# tester_adapter_board.net
KiCad netlist of a schematic drawn in EAGLE
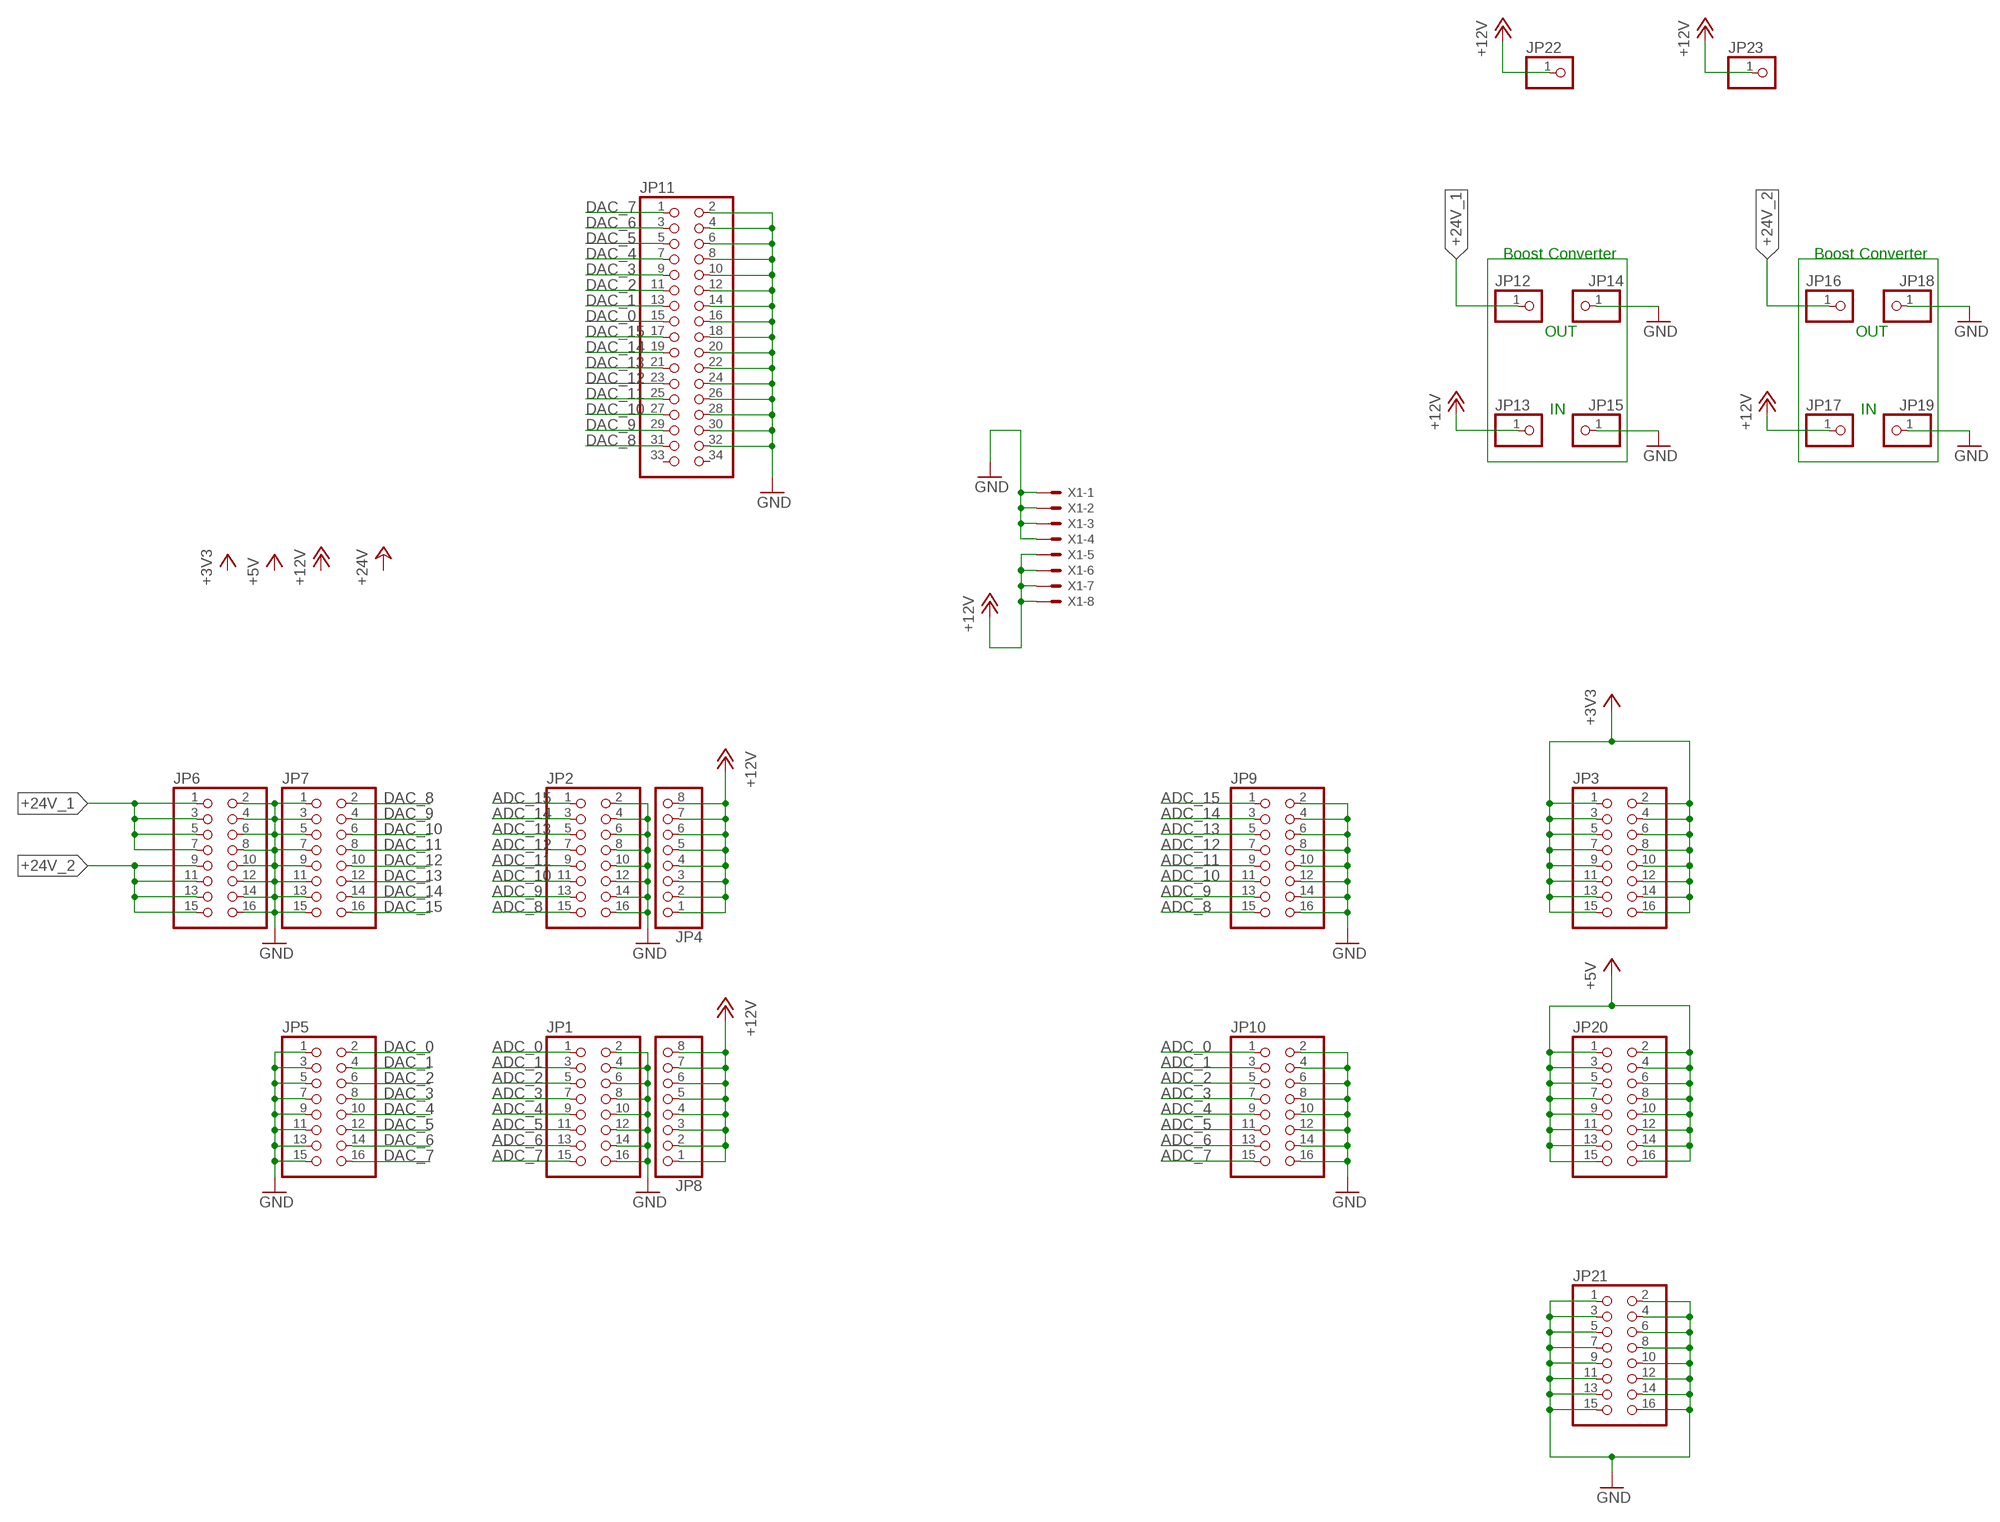
[diagram p0: schematic, sheet 1]

(export (version "E")
  (design (tool "Eeschema 10.0.6"))
  (components
    (comp (ref "JP1")
      (value "PINHD-2X8")
      (footprint "eagle-import:2X08")
      (libsource (lib "eagle-import") (part "PINHD-2X8"))
    )
    (comp (ref "JP2")
      (value "PINHD-2X8")
      (footprint "eagle-import:2X08")
      (libsource (lib "eagle-import") (part "PINHD-2X8"))
    )
    (comp (ref "JP3")
      (value "PINHD-2X8")
      (footprint "eagle-import:2X08")
      (libsource (lib "eagle-import") (part "PINHD-2X8"))
    )
    (comp (ref "JP4")
      (value "PINHD-1X08_2.54-S")
      (footprint "eagle-import:1X08-S")
      (libsource (lib "eagle-import") (part "PINHD-1X08_2.54-S"))
    )
    (comp (ref "JP5")
      (value "PINHD-2X8")
      (footprint "eagle-import:2X08")
      (libsource (lib "eagle-import") (part "PINHD-2X8"))
    )
    (comp (ref "JP6")
      (value "PINHD-2X8")
      (footprint "eagle-import:2X08")
      (libsource (lib "eagle-import") (part "PINHD-2X8"))
    )
    (comp (ref "JP7")
      (value "PINHD-2X8")
      (footprint "eagle-import:2X08")
      (libsource (lib "eagle-import") (part "PINHD-2X8"))
    )
    (comp (ref "JP8")
      (value "PINHD-1X08_2.54-S")
      (footprint "eagle-import:1X08-S")
      (libsource (lib "eagle-import") (part "PINHD-1X08_2.54-S"))
    )
    (comp (ref "JP9")
      (value "PINHD-2X8")
      (footprint "eagle-import:2X08")
      (libsource (lib "eagle-import") (part "PINHD-2X8"))
    )
    (comp (ref "JP10")
      (value "PINHD-2X8")
      (footprint "eagle-import:2X08")
      (libsource (lib "eagle-import") (part "PINHD-2X8"))
    )
    (comp (ref "JP11")
      (value "PINHD-2X17")
      (footprint "eagle-import:2X17")
      (libsource (lib "eagle-import") (part "PINHD-2X17"))
    )
    (comp (ref "JP12")
      (value "PINHD-1X01_2.54")
      (footprint "eagle-import:1X01")
      (libsource (lib "eagle-import") (part "PINHD-1X01_2.54"))
    )
    (comp (ref "JP13")
      (value "PINHD-1X01_2.54")
      (footprint "eagle-import:1X01")
      (libsource (lib "eagle-import") (part "PINHD-1X01_2.54"))
    )
    (comp (ref "JP14")
      (value "PINHD-1X01_2.54-S")
      (footprint "eagle-import:1X01-S")
      (libsource (lib "eagle-import") (part "PINHD-1X01_2.54-S"))
    )
    (comp (ref "JP15")
      (value "PINHD-1X01_2.54-S")
      (footprint "eagle-import:1X01-S")
      (libsource (lib "eagle-import") (part "PINHD-1X01_2.54-S"))
    )
    (comp (ref "JP16")
      (value "PINHD-1X01_2.54")
      (footprint "eagle-import:1X01")
      (libsource (lib "eagle-import") (part "PINHD-1X01_2.54"))
    )
    (comp (ref "JP17")
      (value "PINHD-1X01_2.54")
      (footprint "eagle-import:1X01")
      (libsource (lib "eagle-import") (part "PINHD-1X01_2.54"))
    )
    (comp (ref "JP18")
      (value "PINHD-1X01_2.54-S")
      (footprint "eagle-import:1X01-S")
      (libsource (lib "eagle-import") (part "PINHD-1X01_2.54-S"))
    )
    (comp (ref "JP19")
      (value "PINHD-1X01_2.54-S")
      (footprint "eagle-import:1X01-S")
      (libsource (lib "eagle-import") (part "PINHD-1X01_2.54-S"))
    )
    (comp (ref "JP20")
      (value "PINHD-2X8")
      (footprint "eagle-import:2X08")
      (libsource (lib "eagle-import") (part "PINHD-2X8"))
    )
    (comp (ref "JP21")
      (value "PINHD-2X8")
      (footprint "eagle-import:2X08")
      (libsource (lib "eagle-import") (part "PINHD-2X8"))
    )
    (comp (ref "JP22")
      (value "PINHD-1X01_2.54-SMD")
      (footprint "eagle-import:1X01SMD")
      (libsource (lib "eagle-import") (part "PINHD-1X01_2.54-SMD"))
    )
    (comp (ref "JP23")
      (value "PINHD-1X01_2.54-SMD")
      (footprint "eagle-import:1X01SMD")
      (libsource (lib "eagle-import") (part "PINHD-1X01_2.54-SMD"))
    )
    (comp (ref "X1")
      (value "5566-8")
      (footprint "eagle-import:5566-8")
      (fields (field (name "MF") "MOLEX"))
      (libsource (lib "eagle-import") (part "5566-8"))
    )
  )
  (nets
    (net (code "1") (name "+3V3") (class "Default")
      (node (ref "JP3") (pin "1") (pinfunction "1_1") (pintype "passive"))
      (node (ref "JP3") (pin "10") (pinfunction "10_10") (pintype "passive"))
      (node (ref "JP3") (pin "11") (pinfunction "11_11") (pintype "passive"))
      (node (ref "JP3") (pin "12") (pinfunction "12_12") (pintype "passive"))
      (node (ref "JP3") (pin "13") (pinfunction "13_13") (pintype "passive"))
      (node (ref "JP3") (pin "14") (pinfunction "14_14") (pintype "passive"))
      (node (ref "JP3") (pin "15") (pinfunction "15_15") (pintype "passive"))
      (node (ref "JP3") (pin "16") (pinfunction "16_16") (pintype "passive"))
      (node (ref "JP3") (pin "2") (pinfunction "2_2") (pintype "passive"))
      (node (ref "JP3") (pin "3") (pinfunction "3_3") (pintype "passive"))
      (node (ref "JP3") (pin "4") (pinfunction "4_4") (pintype "passive"))
      (node (ref "JP3") (pin "5") (pinfunction "5_5") (pintype "passive"))
      (node (ref "JP3") (pin "6") (pinfunction "6_6") (pintype "passive"))
      (node (ref "JP3") (pin "7") (pinfunction "7_7") (pintype "passive"))
      (node (ref "JP3") (pin "8") (pinfunction "8_8") (pintype "passive"))
      (node (ref "JP3") (pin "9") (pinfunction "9_9") (pintype "passive"))
    )
    (net (code "2") (name "+5V") (class "Default")
      (node (ref "JP20") (pin "1") (pinfunction "1_1") (pintype "passive"))
      (node (ref "JP20") (pin "10") (pinfunction "10_10") (pintype "passive"))
      (node (ref "JP20") (pin "11") (pinfunction "11_11") (pintype "passive"))
      (node (ref "JP20") (pin "12") (pinfunction "12_12") (pintype "passive"))
      (node (ref "JP20") (pin "13") (pinfunction "13_13") (pintype "passive"))
      (node (ref "JP20") (pin "14") (pinfunction "14_14") (pintype "passive"))
      (node (ref "JP20") (pin "15") (pinfunction "15_15") (pintype "passive"))
      (node (ref "JP20") (pin "16") (pinfunction "16_16") (pintype "passive"))
      (node (ref "JP20") (pin "2") (pinfunction "2_2") (pintype "passive"))
      (node (ref "JP20") (pin "3") (pinfunction "3_3") (pintype "passive"))
      (node (ref "JP20") (pin "4") (pinfunction "4_4") (pintype "passive"))
      (node (ref "JP20") (pin "5") (pinfunction "5_5") (pintype "passive"))
      (node (ref "JP20") (pin "6") (pinfunction "6_6") (pintype "passive"))
      (node (ref "JP20") (pin "7") (pinfunction "7_7") (pintype "passive"))
      (node (ref "JP20") (pin "8") (pinfunction "8_8") (pintype "passive"))
      (node (ref "JP20") (pin "9") (pinfunction "9_9") (pintype "passive"))
    )
    (net (code "3") (name "+12V") (class "Default")
      (node (ref "JP13") (pin "1") (pinfunction "1_1") (pintype "passive"))
      (node (ref "JP17") (pin "1") (pinfunction "1_1") (pintype "passive"))
      (node (ref "JP22") (pin "1") (pinfunction "1_1") (pintype "passive"))
      (node (ref "JP23") (pin "1") (pinfunction "1_1") (pintype "passive"))
      (node (ref "JP4") (pin "1") (pinfunction "1_1") (pintype "passive"))
      (node (ref "JP4") (pin "2") (pinfunction "2_2") (pintype "passive"))
      (node (ref "JP4") (pin "3") (pinfunction "3_3") (pintype "passive"))
      (node (ref "JP4") (pin "4") (pinfunction "4_4") (pintype "passive"))
      (node (ref "JP4") (pin "5") (pinfunction "5_5") (pintype "passive"))
      (node (ref "JP4") (pin "6") (pinfunction "6_6") (pintype "passive"))
      (node (ref "JP4") (pin "7") (pinfunction "7_7") (pintype "passive"))
      (node (ref "JP4") (pin "8") (pinfunction "8_8") (pintype "passive"))
      (node (ref "JP8") (pin "1") (pinfunction "1_1") (pintype "passive"))
      (node (ref "JP8") (pin "2") (pinfunction "2_2") (pintype "passive"))
      (node (ref "JP8") (pin "3") (pinfunction "3_3") (pintype "passive"))
      (node (ref "JP8") (pin "4") (pinfunction "4_4") (pintype "passive"))
      (node (ref "JP8") (pin "5") (pinfunction "5_5") (pintype "passive"))
      (node (ref "JP8") (pin "6") (pinfunction "6_6") (pintype "passive"))
      (node (ref "JP8") (pin "7") (pinfunction "7_7") (pintype "passive"))
      (node (ref "JP8") (pin "8") (pinfunction "8_8") (pintype "passive"))
      (node (ref "X1") (pin "5") (pinfunction "S_5") (pintype "passive"))
      (node (ref "X1") (pin "6") (pinfunction "S_6") (pintype "passive"))
      (node (ref "X1") (pin "7") (pinfunction "S_7") (pintype "passive"))
      (node (ref "X1") (pin "8") (pinfunction "S_8") (pintype "passive"))
    )
    (net (code "5") (name "+24V_1") (class "Default")
      (node (ref "JP12") (pin "1") (pinfunction "1_1") (pintype "passive"))
      (node (ref "JP6") (pin "1") (pinfunction "1_1") (pintype "passive"))
      (node (ref "JP6") (pin "3") (pinfunction "3_3") (pintype "passive"))
      (node (ref "JP6") (pin "5") (pinfunction "5_5") (pintype "passive"))
      (node (ref "JP6") (pin "7") (pinfunction "7_7") (pintype "passive"))
    )
    (net (code "6") (name "+24V_2") (class "Default")
      (node (ref "JP16") (pin "1") (pinfunction "1_1") (pintype "passive"))
      (node (ref "JP6") (pin "11") (pinfunction "11_11") (pintype "passive"))
      (node (ref "JP6") (pin "13") (pinfunction "13_13") (pintype "passive"))
      (node (ref "JP6") (pin "15") (pinfunction "15_15") (pintype "passive"))
      (node (ref "JP6") (pin "9") (pinfunction "9_9") (pintype "passive"))
    )
    (net (code "7") (name "/ADC_0") (class "Default")
      (node (ref "JP1") (pin "1") (pinfunction "1_1") (pintype "passive"))
      (node (ref "JP10") (pin "1") (pinfunction "1_1") (pintype "passive"))
    )
    (net (code "8") (name "/ADC_1") (class "Default")
      (node (ref "JP1") (pin "3") (pinfunction "3_3") (pintype "passive"))
      (node (ref "JP10") (pin "3") (pinfunction "3_3") (pintype "passive"))
    )
    (net (code "9") (name "/ADC_2") (class "Default")
      (node (ref "JP1") (pin "5") (pinfunction "5_5") (pintype "passive"))
      (node (ref "JP10") (pin "5") (pinfunction "5_5") (pintype "passive"))
    )
    (net (code "10") (name "/ADC_3") (class "Default")
      (node (ref "JP1") (pin "7") (pinfunction "7_7") (pintype "passive"))
      (node (ref "JP10") (pin "7") (pinfunction "7_7") (pintype "passive"))
    )
    (net (code "11") (name "/ADC_4") (class "Default")
      (node (ref "JP1") (pin "9") (pinfunction "9_9") (pintype "passive"))
      (node (ref "JP10") (pin "9") (pinfunction "9_9") (pintype "passive"))
    )
    (net (code "12") (name "/ADC_5") (class "Default")
      (node (ref "JP1") (pin "11") (pinfunction "11_11") (pintype "passive"))
      (node (ref "JP10") (pin "11") (pinfunction "11_11") (pintype "passive"))
    )
    (net (code "13") (name "/ADC_6") (class "Default")
      (node (ref "JP1") (pin "13") (pinfunction "13_13") (pintype "passive"))
      (node (ref "JP10") (pin "13") (pinfunction "13_13") (pintype "passive"))
    )
    (net (code "14") (name "/ADC_7") (class "Default")
      (node (ref "JP1") (pin "15") (pinfunction "15_15") (pintype "passive"))
      (node (ref "JP10") (pin "15") (pinfunction "15_15") (pintype "passive"))
    )
    (net (code "15") (name "/ADC_8") (class "Default")
      (node (ref "JP2") (pin "15") (pinfunction "15_15") (pintype "passive"))
      (node (ref "JP9") (pin "15") (pinfunction "15_15") (pintype "passive"))
    )
    (net (code "16") (name "/ADC_9") (class "Default")
      (node (ref "JP2") (pin "13") (pinfunction "13_13") (pintype "passive"))
      (node (ref "JP9") (pin "13") (pinfunction "13_13") (pintype "passive"))
    )
    (net (code "17") (name "/ADC_10") (class "Default")
      (node (ref "JP2") (pin "11") (pinfunction "11_11") (pintype "passive"))
      (node (ref "JP9") (pin "11") (pinfunction "11_11") (pintype "passive"))
    )
    (net (code "18") (name "/ADC_11") (class "Default")
      (node (ref "JP2") (pin "9") (pinfunction "9_9") (pintype "passive"))
      (node (ref "JP9") (pin "9") (pinfunction "9_9") (pintype "passive"))
    )
    (net (code "19") (name "/ADC_12") (class "Default")
      (node (ref "JP2") (pin "7") (pinfunction "7_7") (pintype "passive"))
      (node (ref "JP9") (pin "7") (pinfunction "7_7") (pintype "passive"))
    )
    (net (code "20") (name "/ADC_13") (class "Default")
      (node (ref "JP2") (pin "5") (pinfunction "5_5") (pintype "passive"))
      (node (ref "JP9") (pin "5") (pinfunction "5_5") (pintype "passive"))
    )
    (net (code "21") (name "/ADC_14") (class "Default")
      (node (ref "JP2") (pin "3") (pinfunction "3_3") (pintype "passive"))
      (node (ref "JP9") (pin "3") (pinfunction "3_3") (pintype "passive"))
    )
    (net (code "22") (name "/ADC_15") (class "Default")
      (node (ref "JP2") (pin "1") (pinfunction "1_1") (pintype "passive"))
      (node (ref "JP9") (pin "1") (pinfunction "1_1") (pintype "passive"))
    )
    (net (code "23") (name "/DAC_0") (class "Default")
      (node (ref "JP11") (pin "15") (pinfunction "15_15") (pintype "passive"))
      (node (ref "JP5") (pin "2") (pinfunction "2_2") (pintype "passive"))
    )
    (net (code "24") (name "/DAC_1") (class "Default")
      (node (ref "JP11") (pin "13") (pinfunction "13_13") (pintype "passive"))
      (node (ref "JP5") (pin "4") (pinfunction "4_4") (pintype "passive"))
    )
    (net (code "25") (name "/DAC_2") (class "Default")
      (node (ref "JP11") (pin "11") (pinfunction "11_11") (pintype "passive"))
      (node (ref "JP5") (pin "6") (pinfunction "6_6") (pintype "passive"))
    )
    (net (code "26") (name "/DAC_3") (class "Default")
      (node (ref "JP11") (pin "9") (pinfunction "9_9") (pintype "passive"))
      (node (ref "JP5") (pin "8") (pinfunction "8_8") (pintype "passive"))
    )
    (net (code "27") (name "/DAC_4") (class "Default")
      (node (ref "JP11") (pin "7") (pinfunction "7_7") (pintype "passive"))
      (node (ref "JP5") (pin "10") (pinfunction "10_10") (pintype "passive"))
    )
    (net (code "28") (name "/DAC_5") (class "Default")
      (node (ref "JP11") (pin "5") (pinfunction "5_5") (pintype "passive"))
      (node (ref "JP5") (pin "12") (pinfunction "12_12") (pintype "passive"))
    )
    (net (code "29") (name "/DAC_6") (class "Default")
      (node (ref "JP11") (pin "3") (pinfunction "3_3") (pintype "passive"))
      (node (ref "JP5") (pin "14") (pinfunction "14_14") (pintype "passive"))
    )
    (net (code "30") (name "/DAC_7") (class "Default")
      (node (ref "JP11") (pin "1") (pinfunction "1_1") (pintype "passive"))
      (node (ref "JP5") (pin "16") (pinfunction "16_16") (pintype "passive"))
    )
    (net (code "31") (name "/DAC_8") (class "Default")
      (node (ref "JP11") (pin "31") (pinfunction "31_31") (pintype "passive"))
      (node (ref "JP7") (pin "2") (pinfunction "2_2") (pintype "passive"))
    )
    (net (code "32") (name "/DAC_9") (class "Default")
      (node (ref "JP11") (pin "29") (pinfunction "29_29") (pintype "passive"))
      (node (ref "JP7") (pin "4") (pinfunction "4_4") (pintype "passive"))
    )
    (net (code "33") (name "/DAC_10") (class "Default")
      (node (ref "JP11") (pin "27") (pinfunction "27_27") (pintype "passive"))
      (node (ref "JP7") (pin "6") (pinfunction "6_6") (pintype "passive"))
    )
    (net (code "34") (name "/DAC_11") (class "Default")
      (node (ref "JP11") (pin "25") (pinfunction "25_25") (pintype "passive"))
      (node (ref "JP7") (pin "8") (pinfunction "8_8") (pintype "passive"))
    )
    (net (code "35") (name "/DAC_12") (class "Default")
      (node (ref "JP11") (pin "23") (pinfunction "23_23") (pintype "passive"))
      (node (ref "JP7") (pin "10") (pinfunction "10_10") (pintype "passive"))
    )
    (net (code "36") (name "/DAC_13") (class "Default")
      (node (ref "JP11") (pin "21") (pinfunction "21_21") (pintype "passive"))
      (node (ref "JP7") (pin "12") (pinfunction "12_12") (pintype "passive"))
    )
    (net (code "37") (name "/DAC_14") (class "Default")
      (node (ref "JP11") (pin "19") (pinfunction "19_19") (pintype "passive"))
      (node (ref "JP7") (pin "14") (pinfunction "14_14") (pintype "passive"))
    )
    (net (code "38") (name "/DAC_15") (class "Default")
      (node (ref "JP11") (pin "17") (pinfunction "17_17") (pintype "passive"))
      (node (ref "JP7") (pin "16") (pinfunction "16_16") (pintype "passive"))
    )
    (net (code "39") (name "GND") (class "Default")
      (node (ref "JP1") (pin "10") (pinfunction "10_10") (pintype "passive"))
      (node (ref "JP1") (pin "12") (pinfunction "12_12") (pintype "passive"))
      (node (ref "JP1") (pin "14") (pinfunction "14_14") (pintype "passive"))
      (node (ref "JP1") (pin "16") (pinfunction "16_16") (pintype "passive"))
      (node (ref "JP1") (pin "2") (pinfunction "2_2") (pintype "passive"))
      (node (ref "JP1") (pin "4") (pinfunction "4_4") (pintype "passive"))
      (node (ref "JP1") (pin "6") (pinfunction "6_6") (pintype "passive"))
      (node (ref "JP1") (pin "8") (pinfunction "8_8") (pintype "passive"))
      (node (ref "JP10") (pin "10") (pinfunction "10_10") (pintype "passive"))
      (node (ref "JP10") (pin "12") (pinfunction "12_12") (pintype "passive"))
      (node (ref "JP10") (pin "14") (pinfunction "14_14") (pintype "passive"))
      (node (ref "JP10") (pin "16") (pinfunction "16_16") (pintype "passive"))
      (node (ref "JP10") (pin "2") (pinfunction "2_2") (pintype "passive"))
      (node (ref "JP10") (pin "4") (pinfunction "4_4") (pintype "passive"))
      (node (ref "JP10") (pin "6") (pinfunction "6_6") (pintype "passive"))
      (node (ref "JP10") (pin "8") (pinfunction "8_8") (pintype "passive"))
      (node (ref "JP11") (pin "10") (pinfunction "10_10") (pintype "passive"))
      (node (ref "JP11") (pin "12") (pinfunction "12_12") (pintype "passive"))
      (node (ref "JP11") (pin "14") (pinfunction "14_14") (pintype "passive"))
      (node (ref "JP11") (pin "16") (pinfunction "16_16") (pintype "passive"))
      (node (ref "JP11") (pin "18") (pinfunction "18_18") (pintype "passive"))
      (node (ref "JP11") (pin "2") (pinfunction "2_2") (pintype "passive"))
      (node (ref "JP11") (pin "20") (pinfunction "20_20") (pintype "passive"))
      (node (ref "JP11") (pin "22") (pinfunction "22_22") (pintype "passive"))
      (node (ref "JP11") (pin "24") (pinfunction "24_24") (pintype "passive"))
      (node (ref "JP11") (pin "26") (pinfunction "26_26") (pintype "passive"))
      (node (ref "JP11") (pin "28") (pinfunction "28_28") (pintype "passive"))
      (node (ref "JP11") (pin "30") (pinfunction "30_30") (pintype "passive"))
      (node (ref "JP11") (pin "32") (pinfunction "32_32") (pintype "passive"))
      (node (ref "JP11") (pin "4") (pinfunction "4_4") (pintype "passive"))
      (node (ref "JP11") (pin "6") (pinfunction "6_6") (pintype "passive"))
      (node (ref "JP11") (pin "8") (pinfunction "8_8") (pintype "passive"))
      (node (ref "JP14") (pin "1") (pinfunction "1_1") (pintype "passive"))
      (node (ref "JP15") (pin "1") (pinfunction "1_1") (pintype "passive"))
      (node (ref "JP18") (pin "1") (pinfunction "1_1") (pintype "passive"))
      (node (ref "JP19") (pin "1") (pinfunction "1_1") (pintype "passive"))
      (node (ref "JP2") (pin "10") (pinfunction "10_10") (pintype "passive"))
      (node (ref "JP2") (pin "12") (pinfunction "12_12") (pintype "passive"))
      (node (ref "JP2") (pin "14") (pinfunction "14_14") (pintype "passive"))
      (node (ref "JP2") (pin "16") (pinfunction "16_16") (pintype "passive"))
      (node (ref "JP2") (pin "2") (pinfunction "2_2") (pintype "passive"))
      (node (ref "JP2") (pin "4") (pinfunction "4_4") (pintype "passive"))
      (node (ref "JP2") (pin "6") (pinfunction "6_6") (pintype "passive"))
      (node (ref "JP2") (pin "8") (pinfunction "8_8") (pintype "passive"))
      (node (ref "JP21") (pin "1") (pinfunction "1_1") (pintype "passive"))
      (node (ref "JP21") (pin "10") (pinfunction "10_10") (pintype "passive"))
      (node (ref "JP21") (pin "11") (pinfunction "11_11") (pintype "passive"))
      (node (ref "JP21") (pin "12") (pinfunction "12_12") (pintype "passive"))
      (node (ref "JP21") (pin "13") (pinfunction "13_13") (pintype "passive"))
      (node (ref "JP21") (pin "14") (pinfunction "14_14") (pintype "passive"))
      (node (ref "JP21") (pin "15") (pinfunction "15_15") (pintype "passive"))
      (node (ref "JP21") (pin "16") (pinfunction "16_16") (pintype "passive"))
      (node (ref "JP21") (pin "2") (pinfunction "2_2") (pintype "passive"))
      (node (ref "JP21") (pin "3") (pinfunction "3_3") (pintype "passive"))
      (node (ref "JP21") (pin "4") (pinfunction "4_4") (pintype "passive"))
      (node (ref "JP21") (pin "5") (pinfunction "5_5") (pintype "passive"))
      (node (ref "JP21") (pin "6") (pinfunction "6_6") (pintype "passive"))
      (node (ref "JP21") (pin "7") (pinfunction "7_7") (pintype "passive"))
      (node (ref "JP21") (pin "8") (pinfunction "8_8") (pintype "passive"))
      (node (ref "JP21") (pin "9") (pinfunction "9_9") (pintype "passive"))
      (node (ref "JP5") (pin "1") (pinfunction "1_1") (pintype "passive"))
      (node (ref "JP5") (pin "11") (pinfunction "11_11") (pintype "passive"))
      (node (ref "JP5") (pin "13") (pinfunction "13_13") (pintype "passive"))
      (node (ref "JP5") (pin "15") (pinfunction "15_15") (pintype "passive"))
      (node (ref "JP5") (pin "3") (pinfunction "3_3") (pintype "passive"))
      (node (ref "JP5") (pin "5") (pinfunction "5_5") (pintype "passive"))
      (node (ref "JP5") (pin "7") (pinfunction "7_7") (pintype "passive"))
      (node (ref "JP5") (pin "9") (pinfunction "9_9") (pintype "passive"))
      (node (ref "JP6") (pin "10") (pinfunction "10_10") (pintype "passive"))
      (node (ref "JP6") (pin "12") (pinfunction "12_12") (pintype "passive"))
      (node (ref "JP6") (pin "14") (pinfunction "14_14") (pintype "passive"))
      (node (ref "JP6") (pin "16") (pinfunction "16_16") (pintype "passive"))
      (node (ref "JP6") (pin "2") (pinfunction "2_2") (pintype "passive"))
      (node (ref "JP6") (pin "4") (pinfunction "4_4") (pintype "passive"))
      (node (ref "JP6") (pin "6") (pinfunction "6_6") (pintype "passive"))
      (node (ref "JP6") (pin "8") (pinfunction "8_8") (pintype "passive"))
      (node (ref "JP7") (pin "1") (pinfunction "1_1") (pintype "passive"))
      (node (ref "JP7") (pin "11") (pinfunction "11_11") (pintype "passive"))
      (node (ref "JP7") (pin "13") (pinfunction "13_13") (pintype "passive"))
      (node (ref "JP7") (pin "15") (pinfunction "15_15") (pintype "passive"))
      (node (ref "JP7") (pin "3") (pinfunction "3_3") (pintype "passive"))
      (node (ref "JP7") (pin "5") (pinfunction "5_5") (pintype "passive"))
      (node (ref "JP7") (pin "7") (pinfunction "7_7") (pintype "passive"))
      (node (ref "JP7") (pin "9") (pinfunction "9_9") (pintype "passive"))
      (node (ref "JP9") (pin "10") (pinfunction "10_10") (pintype "passive"))
      (node (ref "JP9") (pin "12") (pinfunction "12_12") (pintype "passive"))
      (node (ref "JP9") (pin "14") (pinfunction "14_14") (pintype "passive"))
      (node (ref "JP9") (pin "16") (pinfunction "16_16") (pintype "passive"))
      (node (ref "JP9") (pin "2") (pinfunction "2_2") (pintype "passive"))
      (node (ref "JP9") (pin "4") (pinfunction "4_4") (pintype "passive"))
      (node (ref "JP9") (pin "6") (pinfunction "6_6") (pintype "passive"))
      (node (ref "JP9") (pin "8") (pinfunction "8_8") (pintype "passive"))
      (node (ref "X1") (pin "1") (pinfunction "S_1") (pintype "passive"))
      (node (ref "X1") (pin "2") (pinfunction "S_2") (pintype "passive"))
      (node (ref "X1") (pin "3") (pinfunction "S_3") (pintype "passive"))
      (node (ref "X1") (pin "4") (pinfunction "S_4") (pintype "passive"))
    )
    (net (code "40") (name "unconnected-(JP11-Pad33)") (class "Default")
      (node (ref "JP11") (pin "33") (pinfunction "33_33") (pintype "passive"))
    )
    (net (code "41") (name "unconnected-(JP11-Pad34)") (class "Default")
      (node (ref "JP11") (pin "34") (pinfunction "34_34") (pintype "passive"))
    )
  )
)
